# BLOCINT.net
KiCad netlist of a schematic drawn in Altium Designer
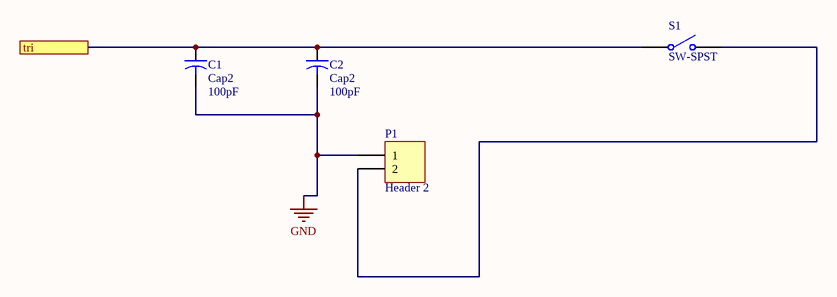
[diagram p0: BLOCINT.SchDoc]

(export (version "E")
  (design (tool "Eeschema 10.0.6"))
  (components
    (comp (ref "C1")
      (value "Cap2")
      (footprint "RB7.6-15")
      (description "Capacitor")
      (fields (field (name "ALTIUM_VALUE") "100pF") (field (name "PUBLISHER") "Altium Limited"))
      (libsource (lib "Miscellaneous Devices") (part "Cap2"))
    )
    (comp (ref "C2")
      (value "Cap2")
      (footprint "RB7.6-15")
      (description "Capacitor")
      (fields (field (name "ALTIUM_VALUE") "100pF") (field (name "PUBLISHER") "Altium Limited"))
      (libsource (lib "Miscellaneous Devices") (part "Cap2"))
    )
    (comp (ref "P1")
      (value "Header 2")
      (footprint "HDR1X2")
      (description "Header, 2-Pin")
      (fields (field (name "PUBLISHER") "Altium Limited"))
      (libsource (lib "Miscellaneous Connectors") (part "Header 2"))
    )
    (comp (ref "S1")
      (value "SW-SPST")
      (footprint "SPST-2")
      (description "Single-Pole, Single-Throw Switch")
      (fields (field (name "PUBLISHER") "Altium Limited"))
      (libsource (lib "Miscellaneous Devices") (part "SW-SPST"))
    )
  )
  (nets
    (net (code "1") (name "/tri") (class "Default")
      (node (ref "C1") (pin "1") (pinfunction "1_1") (pintype "passive"))
      (node (ref "C2") (pin "1") (pinfunction "1_1") (pintype "passive"))
      (node (ref "S1") (pin "1") (pinfunction "COMMON_1") (pintype "passive"))
    )
    (net (code "2") (name "GND") (class "Default")
      (node (ref "C1") (pin "2") (pinfunction "2_2") (pintype "passive"))
      (node (ref "C2") (pin "2") (pinfunction "2_2") (pintype "passive"))
      (node (ref "P1") (pin "1") (pinfunction "1_1") (pintype "passive"))
    )
    (net (code "3") (name "Net-(S1-NO)") (class "Default")
      (node (ref "P1") (pin "2") (pinfunction "2_2") (pintype "passive"))
      (node (ref "S1") (pin "2") (pinfunction "NO_2") (pintype "passive"))
    )
  )
)
